# Motherboard.net
KiCad netlist of a schematic drawn in EAGLE
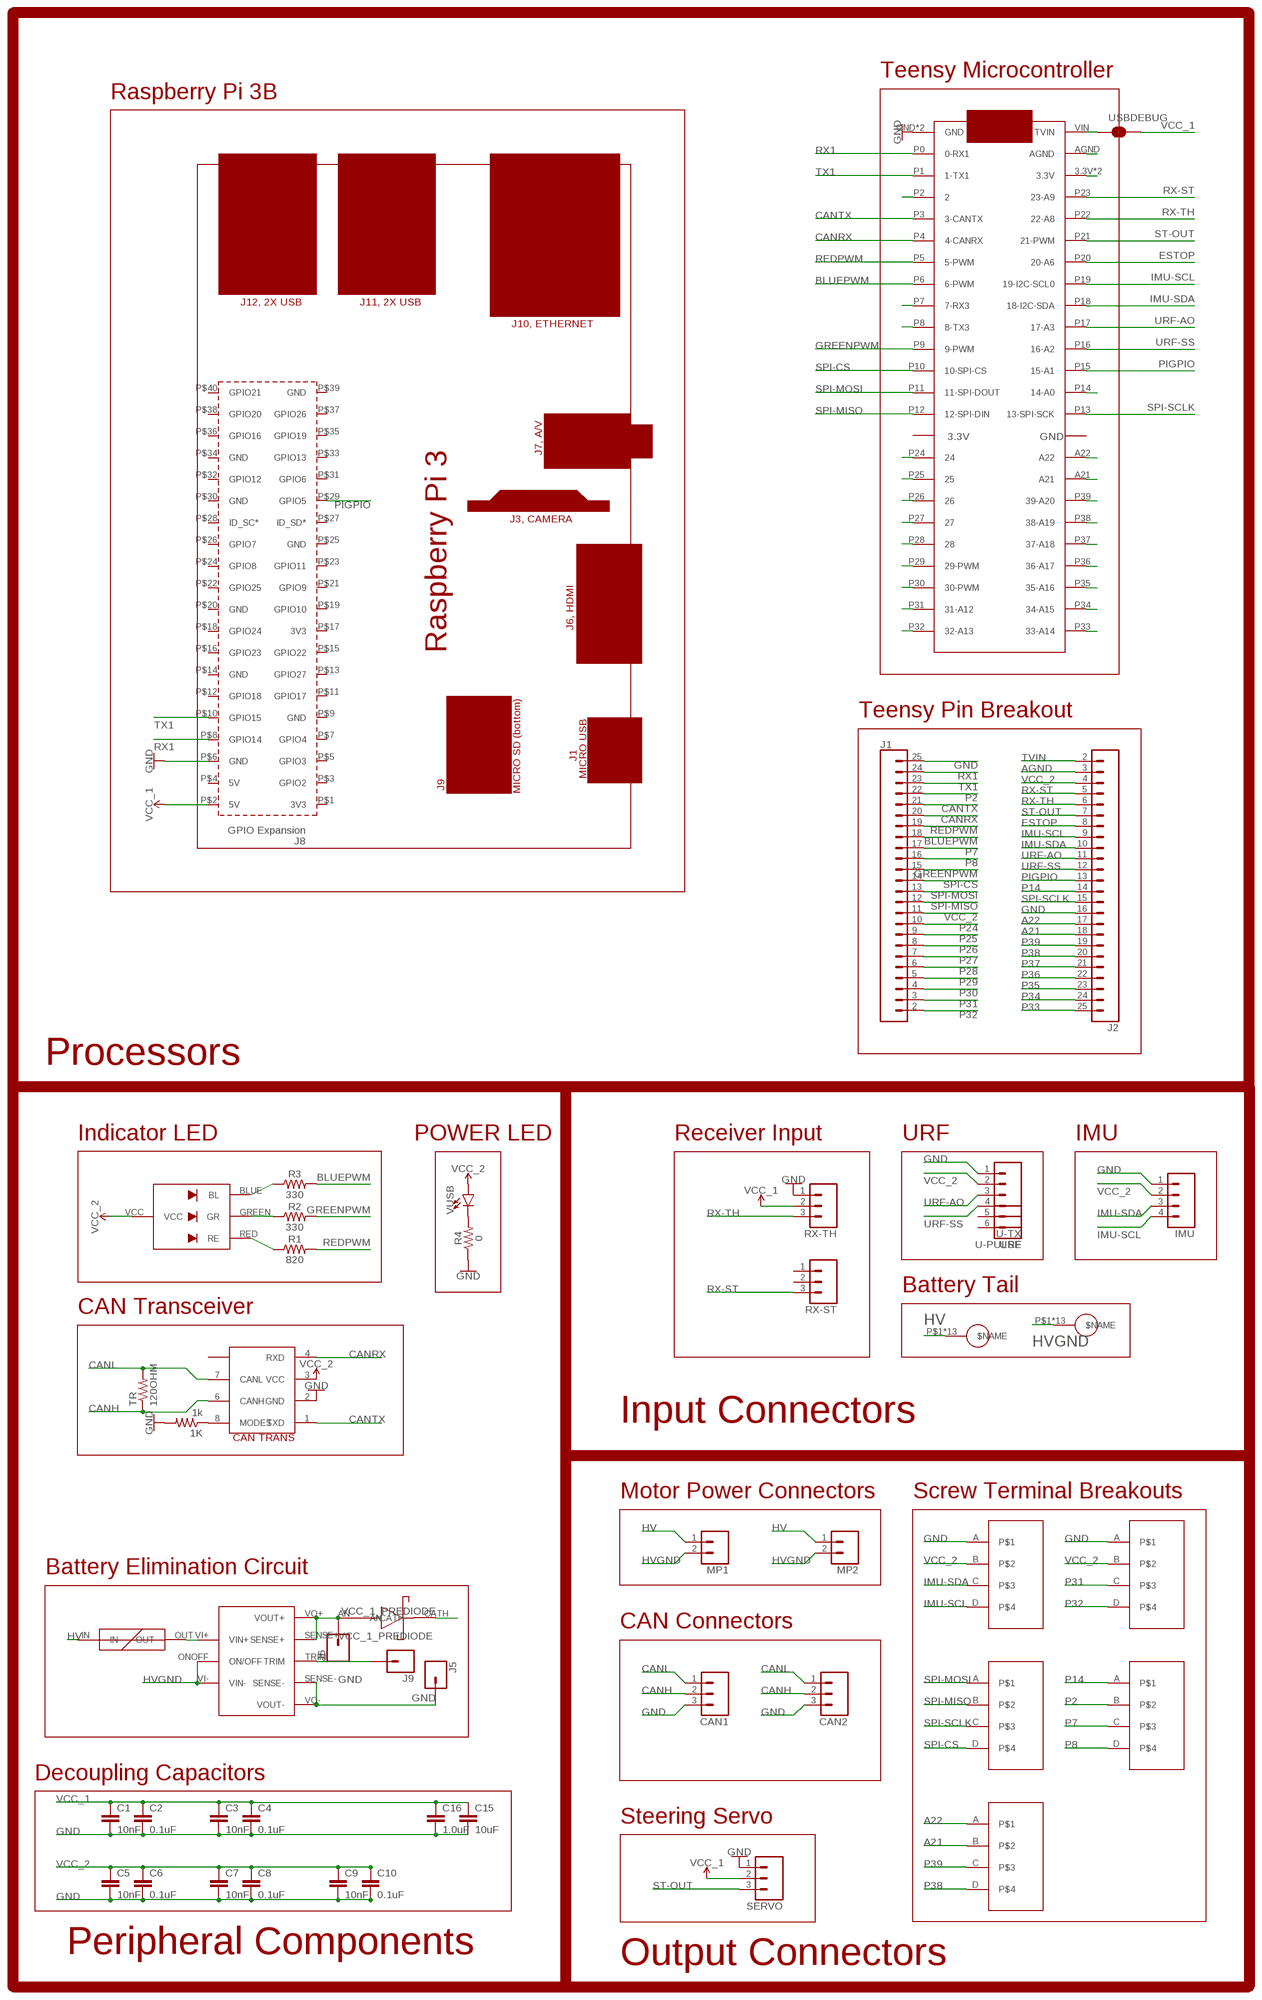
[diagram p0: schematic, sheet 1]

(export (version "E")
  (design (tool "Eeschema 10.0.6"))
  (components
    (comp (ref "1K")
      (value "1k")
      (footprint "eagle-import:R0603")
      (libsource (lib "eagle-import") (part "R-US_R0603"))
    )
    (comp (ref "C1")
      (value "10nF")
      (footprint "eagle-import:0603")
      (libsource (lib "eagle-import") (part "10NF-0603-50V-10%"))
    )
    (comp (ref "C2")
      (value "0.1uF")
      (footprint "eagle-import:0603")
      (libsource (lib "eagle-import") (part "0.1UF-0603-25V-(+80/-20%)"))
    )
    (comp (ref "C3")
      (value "10nF")
      (footprint "eagle-import:0603")
      (libsource (lib "eagle-import") (part "10NF-0603-50V-10%"))
    )
    (comp (ref "C4")
      (value "0.1uF")
      (footprint "eagle-import:0603")
      (libsource (lib "eagle-import") (part "0.1UF-0603-25V-(+80/-20%)"))
    )
    (comp (ref "C5")
      (value "10nF")
      (footprint "eagle-import:0603")
      (libsource (lib "eagle-import") (part "10NF-0603-50V-10%"))
    )
    (comp (ref "C6")
      (value "0.1uF")
      (footprint "eagle-import:0603")
      (libsource (lib "eagle-import") (part "0.1UF-0603-25V-(+80/-20%)"))
    )
    (comp (ref "C7")
      (value "10nF")
      (footprint "eagle-import:0603")
      (libsource (lib "eagle-import") (part "10NF-0603-50V-10%"))
    )
    (comp (ref "C8")
      (value "0.1uF")
      (footprint "eagle-import:0603")
      (libsource (lib "eagle-import") (part "0.1UF-0603-25V-(+80/-20%)"))
    )
    (comp (ref "C9")
      (value "10nF")
      (footprint "eagle-import:0603")
      (libsource (lib "eagle-import") (part "10NF-0603-50V-10%"))
    )
    (comp (ref "C10")
      (value "0.1uF")
      (footprint "eagle-import:0603")
      (libsource (lib "eagle-import") (part "0.1UF-0603-25V-(+80/-20%)"))
    )
    (comp (ref "C15")
      (value "10uF")
      (footprint "eagle-import:1206")
      (libsource (lib "eagle-import") (part "10UF-1206-6.3V-20%"))
    )
    (comp (ref "C16")
      (value "1.0uF")
      (footprint "eagle-import:1206")
      (libsource (lib "eagle-import") (part "1.0UF-1206-50V-10%"))
    )
    (comp (ref "CAN1")
      (value "CONN_03SCREW")
      (footprint "eagle-import:SCREWTERMINAL-3.5MM-3")
      (libsource (lib "eagle-import") (part "CONN_03SCREW"))
    )
    (comp (ref "CAN2")
      (value "CONN_03SCREW")
      (footprint "eagle-import:SCREWTERMINAL-3.5MM-3")
      (libsource (lib "eagle-import") (part "CONN_03SCREW"))
    )
    (comp (ref "DAC/ADC")
      (value "SCREWTERM")
      (footprint "eagle-import:SCREWTERM")
      (libsource (lib "eagle-import") (part "SCREWTERM"))
    )
    (comp (ref "HV+")
      (value "WIREPAD")
      (footprint "eagle-import:WIREPAD")
      (libsource (lib "eagle-import") (part "WIREPAD"))
    )
    (comp (ref "HV-")
      (value "WIREPAD")
      (footprint "eagle-import:WIREPAD")
      (libsource (lib "eagle-import") (part "WIREPAD"))
    )
    (comp (ref "I2C")
      (value "SCREWTERM")
      (footprint "eagle-import:SCREWTERM")
      (libsource (lib "eagle-import") (part "SCREWTERM"))
    )
    (comp (ref "IMU")
      (value "CONN_041X04_NO_SILK")
      (footprint "eagle-import:1X04_NO_SILK")
      (libsource (lib "eagle-import") (part "CONN_041X04_NO_SILK"))
    )
    (comp (ref "J1")
      (value "CONN_24")
      (footprint "eagle-import:1X24")
      (libsource (lib "eagle-import") (part "CONN_24"))
    )
    (comp (ref "J2")
      (value "CONN_24")
      (footprint "eagle-import:1X24")
      (libsource (lib "eagle-import") (part "CONN_24"))
    )
    (comp (ref "J5")
      (value "CONN_01PTH_NO_SILK_YES_STOP")
      (footprint "eagle-import:1X01_NO_SILK")
      (libsource (lib "eagle-import") (part "CONN_01PTH_NO_SILK_YES_STOP"))
    )
    (comp (ref "J6")
      (value "CONN_01PTH_NO_SILK_YES_STOP")
      (footprint "eagle-import:1X01_NO_SILK")
      (libsource (lib "eagle-import") (part "CONN_01PTH_NO_SILK_YES_STOP"))
    )
    (comp (ref "J9")
      (value "CONN_01PTH_NO_SILK_YES_STOP")
      (footprint "eagle-import:1X01_NO_SILK")
      (libsource (lib "eagle-import") (part "CONN_01PTH_NO_SILK_YES_STOP"))
    )
    (comp (ref "MP1")
      (value "CONN_023.5MM")
      (footprint "eagle-import:SCREWTERMINAL-3.5MM-2")
      (libsource (lib "eagle-import") (part "CONN_023.5MM"))
    )
    (comp (ref "MP2")
      (value "CONN_023.5MM")
      (footprint "eagle-import:SCREWTERMINAL-3.5MM-2")
      (libsource (lib "eagle-import") (part "CONN_023.5MM"))
    )
    (comp (ref "PCB1")
      (value "RPI3")
      (footprint "eagle-import:RPI3")
      (libsource (lib "eagle-import") (part "RPI3"))
    )
    (comp (ref "PWM")
      (value "SCREWTERM")
      (footprint "eagle-import:SCREWTERM")
      (libsource (lib "eagle-import") (part "SCREWTERM"))
    )
    (comp (ref "R1")
      (value "820")
      (footprint "eagle-import:0603")
      (libsource (lib "eagle-import") (part "0OHM-0603-1/10W-5%"))
    )
    (comp (ref "R2")
      (value "330")
      (footprint "eagle-import:0603")
      (libsource (lib "eagle-import") (part "0OHM-0603-1/10W-5%"))
    )
    (comp (ref "R3")
      (value "330")
      (footprint "eagle-import:0603")
      (libsource (lib "eagle-import") (part "0OHM-0603-1/10W-5%"))
    )
    (comp (ref "R4")
      (value "0")
      (footprint "eagle-import:0603")
      (libsource (lib "eagle-import") (part "0OHM-0603-1/10W-5%"))
    )
    (comp (ref "RPI-SPI")
      (value "SCREWTERM")
      (footprint "eagle-import:SCREWTERM")
      (libsource (lib "eagle-import") (part "SCREWTERM"))
    )
    (comp (ref "RX-ST")
      (value "CONN_03")
      (footprint "eagle-import:1X03")
      (libsource (lib "eagle-import") (part "CONN_03"))
    )
    (comp (ref "RX-TH")
      (value "CONN_03")
      (footprint "eagle-import:1X03")
      (libsource (lib "eagle-import") (part "CONN_03"))
    )
    (comp (ref "SERVO")
      (value "CONN_03")
      (footprint "eagle-import:1X03")
      (libsource (lib "eagle-import") (part "CONN_03"))
    )
    (comp (ref "TEENS")
      (value "TEENSY3.6")
      (footprint "eagle-import:TEENSY3.6")
      (libsource (lib "eagle-import") (part "TEENSY3.6"))
    )
    (comp (ref "TR")
      (value "120OHM")
      (footprint "eagle-import:R0603")
      (libsource (lib "eagle-import") (part "R-US_R0603"))
    )
    (comp (ref "U$1")
      (value "CREERGB")
      (footprint "eagle-import:CREERGB")
      (libsource (lib "eagle-import") (part "CREERGB"))
    )
    (comp (ref "U$2")
      (value "CAN-TRANS")
      (footprint "eagle-import:SO08")
      (libsource (lib "eagle-import") (part "CAN-TRANS"))
    )
    (comp (ref "U$4")
      (value "BEC")
      (footprint "eagle-import:BEC")
      (libsource (lib "eagle-import") (part "BEC"))
    )
    (comp (ref "U$5")
      (value "LITTLEFUSE")
      (footprint "eagle-import:LITTLEFUSE")
      (libsource (lib "eagle-import") (part "LITTLEFUSE"))
    )
    (comp (ref "U$6")
      (value "SCHOTTKY")
      (footprint "eagle-import:2114")
      (libsource (lib "eagle-import") (part "SCHOTTKY"))
    )
    (comp (ref "U-PULSE")
      (value "CONN_01PTH_NO_SILK_YES_STOP")
      (footprint "eagle-import:1X01_NO_SILK")
      (libsource (lib "eagle-import") (part "CONN_01PTH_NO_SILK_YES_STOP"))
    )
    (comp (ref "U-TX")
      (value "CONN_01PTH_NO_SILK_YES_STOP")
      (footprint "eagle-import:1X01_NO_SILK")
      (libsource (lib "eagle-import") (part "CONN_01PTH_NO_SILK_YES_STOP"))
    )
    (comp (ref "UART")
      (value "SCREWTERM")
      (footprint "eagle-import:SCREWTERM")
      (libsource (lib "eagle-import") (part "SCREWTERM"))
    )
    (comp (ref "URF")
      (value "CONN_06NO_SILK_FEMALE_PTH")
      (footprint "eagle-import:1X06_NO_SILK")
      (libsource (lib "eagle-import") (part "CONN_06NO_SILK_FEMALE_PTH"))
    )
    (comp (ref "USBDEBUG")
      (value "JUMPER-SMT_2_NO_NO-SILK")
      (footprint "eagle-import:SMT-JUMPER_2_NO_NO-SILK")
      (libsource (lib "eagle-import") (part "JUMPER-SMT_2_NO_NO-SILK"))
    )
    (comp (ref "VUSB")
      (value "LED0603")
      (footprint "eagle-import:LED-0603")
      (libsource (lib "eagle-import") (part "LED0603"))
    )
  )
  (nets
    (net (code "1") (name "/A21") (class "Default")
      (node (ref "DAC/ADC") (pin "B") (pinfunction "P$2_B") (pintype "bidirectional"))
      (node (ref "J2") (pin "18") (pinfunction "18_18") (pintype "passive"))
      (node (ref "TEENS") (pin "A21") (pinfunction "A21_A21") (pintype "bidirectional"))
    )
    (net (code "2") (name "/A22") (class "Default")
      (node (ref "DAC/ADC") (pin "A") (pinfunction "P$1_A") (pintype "bidirectional"))
      (node (ref "J2") (pin "17") (pinfunction "17_17") (pintype "passive"))
      (node (ref "TEENS") (pin "A22") (pinfunction "A22_A22") (pintype "bidirectional"))
    )
    (net (code "3") (name "/AGND") (class "Default")
      (node (ref "J2") (pin "3") (pinfunction "3_3") (pintype "passive"))
      (node (ref "TEENS") (pin "AGND") (pinfunction "AGND_AGND") (pintype "bidirectional"))
    )
    (net (code "4") (name "/BLUEPWM") (class "Default")
      (node (ref "J1") (pin "18") (pinfunction "18_18") (pintype "passive"))
      (node (ref "R3") (pin "2") (pinfunction "2_2") (pintype "passive"))
      (node (ref "TEENS") (pin "P6") (pinfunction "6-PWM_P6") (pintype "bidirectional"))
    )
    (net (code "5") (name "/CANH") (class "Default")
      (node (ref "CAN1") (pin "2") (pinfunction "2_2") (pintype "passive"))
      (node (ref "CAN2") (pin "2") (pinfunction "2_2") (pintype "passive"))
      (node (ref "TR") (pin "1") (pinfunction "1_1") (pintype "passive"))
      (node (ref "U$2") (pin "6") (pinfunction "CANH_6") (pintype "bidirectional"))
    )
    (net (code "6") (name "/CANL") (class "Default")
      (node (ref "CAN1") (pin "1") (pinfunction "1_1") (pintype "passive"))
      (node (ref "CAN2") (pin "1") (pinfunction "1_1") (pintype "passive"))
      (node (ref "TR") (pin "2") (pinfunction "2_2") (pintype "passive"))
      (node (ref "U$2") (pin "7") (pinfunction "CANL_7") (pintype "bidirectional"))
    )
    (net (code "7") (name "/CANRX") (class "Default")
      (node (ref "J1") (pin "20") (pinfunction "20_20") (pintype "passive"))
      (node (ref "TEENS") (pin "P4") (pinfunction "4-CANRX_P4") (pintype "bidirectional"))
      (node (ref "U$2") (pin "4") (pinfunction "RXD_4") (pintype "bidirectional"))
    )
    (net (code "8") (name "/CANTX") (class "Default")
      (node (ref "J1") (pin "21") (pinfunction "21_21") (pintype "passive"))
      (node (ref "TEENS") (pin "P3") (pinfunction "3-CANTX_P3") (pintype "bidirectional"))
      (node (ref "U$2") (pin "1") (pinfunction "TXD_1") (pintype "bidirectional"))
    )
    (net (code "9") (name "/ESTOP") (class "Default")
      (node (ref "J2") (pin "8") (pinfunction "8_8") (pintype "passive"))
      (node (ref "TEENS") (pin "P20") (pinfunction "20-A6_P20") (pintype "bidirectional"))
    )
    (net (code "10") (name "/GREENPWM") (class "Default")
      (node (ref "J1") (pin "15") (pinfunction "15_15") (pintype "passive"))
      (node (ref "R2") (pin "2") (pinfunction "2_2") (pintype "passive"))
      (node (ref "TEENS") (pin "P9") (pinfunction "9-PWM_P9") (pintype "bidirectional"))
    )
    (net (code "11") (name "/HV") (class "Default")
      (node (ref "HV+") (pin "P$1") (pinfunction "$NAME_P$1") (pintype "bidirectional"))
      (node (ref "HV+") (pin "P$10") (pinfunction "$NAME_P$10") (pintype "bidirectional"))
      (node (ref "HV+") (pin "P$11") (pinfunction "$NAME_P$11") (pintype "bidirectional"))
      (node (ref "HV+") (pin "P$12") (pinfunction "$NAME_P$12") (pintype "bidirectional"))
      (node (ref "HV+") (pin "P$13") (pinfunction "$NAME_P$13") (pintype "bidirectional"))
      (node (ref "HV+") (pin "P$2") (pinfunction "$NAME_P$2") (pintype "bidirectional"))
      (node (ref "HV+") (pin "P$3") (pinfunction "$NAME_P$3") (pintype "bidirectional"))
      (node (ref "HV+") (pin "P$4") (pinfunction "$NAME_P$4") (pintype "bidirectional"))
      (node (ref "HV+") (pin "P$5") (pinfunction "$NAME_P$5") (pintype "bidirectional"))
      (node (ref "HV+") (pin "P$6") (pinfunction "$NAME_P$6") (pintype "bidirectional"))
      (node (ref "HV+") (pin "P$7") (pinfunction "$NAME_P$7") (pintype "bidirectional"))
      (node (ref "HV+") (pin "P$8") (pinfunction "$NAME_P$8") (pintype "bidirectional"))
      (node (ref "HV+") (pin "P$9") (pinfunction "$NAME_P$9") (pintype "bidirectional"))
      (node (ref "MP1") (pin "1") (pinfunction "1_1") (pintype "passive"))
      (node (ref "MP2") (pin "1") (pinfunction "1_1") (pintype "passive"))
      (node (ref "U$5") (pin "IN") (pinfunction "IN_IN") (pintype "bidirectional"))
    )
    (net (code "12") (name "/HVGND") (class "Default")
      (node (ref "HV-") (pin "P$1") (pinfunction "$NAME_P$1") (pintype "bidirectional"))
      (node (ref "HV-") (pin "P$10") (pinfunction "$NAME_P$10") (pintype "bidirectional"))
      (node (ref "HV-") (pin "P$11") (pinfunction "$NAME_P$11") (pintype "bidirectional"))
      (node (ref "HV-") (pin "P$12") (pinfunction "$NAME_P$12") (pintype "bidirectional"))
      (node (ref "HV-") (pin "P$13") (pinfunction "$NAME_P$13") (pintype "bidirectional"))
      (node (ref "HV-") (pin "P$2") (pinfunction "$NAME_P$2") (pintype "bidirectional"))
      (node (ref "HV-") (pin "P$3") (pinfunction "$NAME_P$3") (pintype "bidirectional"))
      (node (ref "HV-") (pin "P$4") (pinfunction "$NAME_P$4") (pintype "bidirectional"))
      (node (ref "HV-") (pin "P$5") (pinfunction "$NAME_P$5") (pintype "bidirectional"))
      (node (ref "HV-") (pin "P$6") (pinfunction "$NAME_P$6") (pintype "bidirectional"))
      (node (ref "HV-") (pin "P$7") (pinfunction "$NAME_P$7") (pintype "bidirectional"))
      (node (ref "HV-") (pin "P$8") (pinfunction "$NAME_P$8") (pintype "bidirectional"))
      (node (ref "HV-") (pin "P$9") (pinfunction "$NAME_P$9") (pintype "bidirectional"))
      (node (ref "MP1") (pin "2") (pinfunction "2_2") (pintype "passive"))
      (node (ref "MP2") (pin "2") (pinfunction "2_2") (pintype "passive"))
      (node (ref "U$4") (pin "ONOFF") (pinfunction "ON/OFF_ONOFF") (pintype "bidirectional"))
      (node (ref "U$4") (pin "VI-") (pinfunction "VIN-_VI-") (pintype "bidirectional"))
    )
    (net (code "13") (name "/IMU-SCL") (class "Default")
      (node (ref "I2C") (pin "D") (pinfunction "P$4_D") (pintype "bidirectional"))
      (node (ref "IMU") (pin "4") (pinfunction "4_4") (pintype "passive"))
      (node (ref "J2") (pin "9") (pinfunction "9_9") (pintype "passive"))
      (node (ref "TEENS") (pin "P19") (pinfunction "19-I2C-SCL0_P19") (pintype "bidirectional"))
    )
    (net (code "14") (name "/IMU-SDA") (class "Default")
      (node (ref "I2C") (pin "C") (pinfunction "P$3_C") (pintype "bidirectional"))
      (node (ref "IMU") (pin "3") (pinfunction "3_3") (pintype "passive"))
      (node (ref "J2") (pin "10") (pinfunction "10_10") (pintype "passive"))
      (node (ref "TEENS") (pin "P18") (pinfunction "18-I2C-SDA_P18") (pintype "bidirectional"))
    )
    (net (code "15") (name "/P2") (class "Default")
      (node (ref "J1") (pin "22") (pinfunction "22_22") (pintype "passive"))
      (node (ref "PWM") (pin "B") (pinfunction "P$2_B") (pintype "bidirectional"))
      (node (ref "TEENS") (pin "P2") (pinfunction "2_P2") (pintype "bidirectional"))
    )
    (net (code "16") (name "/P7") (class "Default")
      (node (ref "J1") (pin "17") (pinfunction "17_17") (pintype "passive"))
      (node (ref "PWM") (pin "C") (pinfunction "P$3_C") (pintype "bidirectional"))
      (node (ref "TEENS") (pin "P7") (pinfunction "7-RX3_P7") (pintype "bidirectional"))
    )
    (net (code "17") (name "/P8") (class "Default")
      (node (ref "J1") (pin "16") (pinfunction "16_16") (pintype "passive"))
      (node (ref "PWM") (pin "D") (pinfunction "P$4_D") (pintype "bidirectional"))
      (node (ref "TEENS") (pin "P8") (pinfunction "8-TX3_P8") (pintype "bidirectional"))
    )
    (net (code "18") (name "/P14") (class "Default")
      (node (ref "J2") (pin "14") (pinfunction "14_14") (pintype "passive"))
      (node (ref "PWM") (pin "A") (pinfunction "P$1_A") (pintype "bidirectional"))
      (node (ref "TEENS") (pin "P14") (pinfunction "14-A0_P14") (pintype "bidirectional"))
    )
    (net (code "19") (name "/P24") (class "Default")
      (node (ref "J1") (pin "10") (pinfunction "10_10") (pintype "passive"))
      (node (ref "TEENS") (pin "P24") (pinfunction "24_P24") (pintype "bidirectional"))
    )
    (net (code "20") (name "/P25") (class "Default")
      (node (ref "J1") (pin "9") (pinfunction "9_9") (pintype "passive"))
      (node (ref "TEENS") (pin "P25") (pinfunction "25_P25") (pintype "bidirectional"))
    )
    (net (code "21") (name "/P26") (class "Default")
      (node (ref "J1") (pin "8") (pinfunction "8_8") (pintype "passive"))
      (node (ref "TEENS") (pin "P26") (pinfunction "26_P26") (pintype "bidirectional"))
    )
    (net (code "22") (name "/P27") (class "Default")
      (node (ref "J1") (pin "7") (pinfunction "7_7") (pintype "passive"))
      (node (ref "TEENS") (pin "P27") (pinfunction "27_P27") (pintype "bidirectional"))
    )
    (net (code "23") (name "/P28") (class "Default")
      (node (ref "J1") (pin "6") (pinfunction "6_6") (pintype "passive"))
      (node (ref "TEENS") (pin "P28") (pinfunction "28_P28") (pintype "bidirectional"))
    )
    (net (code "24") (name "/P29") (class "Default")
      (node (ref "J1") (pin "5") (pinfunction "5_5") (pintype "passive"))
      (node (ref "TEENS") (pin "P29") (pinfunction "29-PWM_P29") (pintype "bidirectional"))
    )
    (net (code "25") (name "/P30") (class "Default")
      (node (ref "J1") (pin "4") (pinfunction "4_4") (pintype "passive"))
      (node (ref "TEENS") (pin "P30") (pinfunction "30-PWM_P30") (pintype "bidirectional"))
    )
    (net (code "26") (name "/P31") (class "Default")
      (node (ref "J1") (pin "3") (pinfunction "3_3") (pintype "passive"))
      (node (ref "TEENS") (pin "P31") (pinfunction "31-A12_P31") (pintype "bidirectional"))
      (node (ref "UART") (pin "C") (pinfunction "P$3_C") (pintype "bidirectional"))
    )
    (net (code "27") (name "/P32") (class "Default")
      (node (ref "J1") (pin "2") (pinfunction "2_2") (pintype "passive"))
      (node (ref "TEENS") (pin "P32") (pinfunction "32-A13_P32") (pintype "bidirectional"))
      (node (ref "UART") (pin "D") (pinfunction "P$4_D") (pintype "bidirectional"))
    )
    (net (code "28") (name "/P33") (class "Default")
      (node (ref "J2") (pin "25") (pinfunction "25_25") (pintype "passive"))
      (node (ref "TEENS") (pin "P33") (pinfunction "33-A14_P33") (pintype "bidirectional"))
    )
    (net (code "29") (name "/P34") (class "Default")
      (node (ref "J2") (pin "24") (pinfunction "24_24") (pintype "passive"))
      (node (ref "TEENS") (pin "P34") (pinfunction "34-A15_P34") (pintype "bidirectional"))
    )
    (net (code "30") (name "/P35") (class "Default")
      (node (ref "J2") (pin "23") (pinfunction "23_23") (pintype "passive"))
      (node (ref "TEENS") (pin "P35") (pinfunction "35-A16_P35") (pintype "bidirectional"))
    )
    (net (code "31") (name "/P36") (class "Default")
      (node (ref "J2") (pin "22") (pinfunction "22_22") (pintype "passive"))
      (node (ref "TEENS") (pin "P36") (pinfunction "36-A17_P36") (pintype "bidirectional"))
    )
    (net (code "32") (name "/P37") (class "Default")
      (node (ref "J2") (pin "21") (pinfunction "21_21") (pintype "passive"))
      (node (ref "TEENS") (pin "P37") (pinfunction "37-A18_P37") (pintype "bidirectional"))
    )
    (net (code "33") (name "/P38") (class "Default")
      (node (ref "DAC/ADC") (pin "D") (pinfunction "P$4_D") (pintype "bidirectional"))
      (node (ref "J2") (pin "20") (pinfunction "20_20") (pintype "passive"))
      (node (ref "TEENS") (pin "P38") (pinfunction "38-A19_P38") (pintype "bidirectional"))
    )
    (net (code "34") (name "/P39") (class "Default")
      (node (ref "DAC/ADC") (pin "C") (pinfunction "P$3_C") (pintype "bidirectional"))
      (node (ref "J2") (pin "19") (pinfunction "19_19") (pintype "passive"))
      (node (ref "TEENS") (pin "P39") (pinfunction "39-A20_P39") (pintype "bidirectional"))
    )
    (net (code "35") (name "/PIGPIO") (class "Default")
      (node (ref "J2") (pin "13") (pinfunction "13_13") (pintype "passive"))
      (node (ref "PCB1") (pin "P$29") (pinfunction "GPIO5_P$29") (pintype "bidirectional"))
      (node (ref "TEENS") (pin "P15") (pinfunction "15-A1_P15") (pintype "bidirectional"))
    )
    (net (code "36") (name "/REDPWM") (class "Default")
      (node (ref "J1") (pin "19") (pinfunction "19_19") (pintype "passive"))
      (node (ref "R1") (pin "2") (pinfunction "2_2") (pintype "passive"))
      (node (ref "TEENS") (pin "P5") (pinfunction "5-PWM_P5") (pintype "bidirectional"))
    )
    (net (code "37") (name "/RX-ST") (class "Default")
      (node (ref "J2") (pin "5") (pinfunction "5_5") (pintype "passive"))
      (node (ref "RX-ST") (pin "3") (pinfunction "3_3") (pintype "passive"))
      (node (ref "TEENS") (pin "P23") (pinfunction "23-A9_P23") (pintype "bidirectional"))
    )
    (net (code "38") (name "/RX-TH") (class "Default")
      (node (ref "J2") (pin "6") (pinfunction "6_6") (pintype "passive"))
      (node (ref "RX-TH") (pin "3") (pinfunction "3_3") (pintype "passive"))
      (node (ref "TEENS") (pin "P22") (pinfunction "22-A8_P22") (pintype "bidirectional"))
    )
    (net (code "39") (name "/RX1") (class "Default")
      (node (ref "J1") (pin "24") (pinfunction "24_24") (pintype "passive"))
      (node (ref "PCB1") (pin "P$8") (pinfunction "GPIO14_P$8") (pintype "bidirectional"))
      (node (ref "TEENS") (pin "P0") (pinfunction "0-RX1_P0") (pintype "bidirectional"))
    )
    (net (code "40") (name "/SPI-CS") (class "Default")
      (node (ref "J1") (pin "14") (pinfunction "14_14") (pintype "passive"))
      (node (ref "RPI-SPI") (pin "D") (pinfunction "P$4_D") (pintype "bidirectional"))
      (node (ref "TEENS") (pin "P10") (pinfunction "10-SPI-CS_P10") (pintype "bidirectional"))
    )
    (net (code "41") (name "/SPI-MISO") (class "Default")
      (node (ref "J1") (pin "12") (pinfunction "12_12") (pintype "passive"))
      (node (ref "RPI-SPI") (pin "B") (pinfunction "P$2_B") (pintype "bidirectional"))
      (node (ref "TEENS") (pin "P12") (pinfunction "12-SPI-DIN_P12") (pintype "bidirectional"))
    )
    (net (code "42") (name "/SPI-MOSI") (class "Default")
      (node (ref "J1") (pin "13") (pinfunction "13_13") (pintype "passive"))
      (node (ref "RPI-SPI") (pin "A") (pinfunction "P$1_A") (pintype "bidirectional"))
      (node (ref "TEENS") (pin "P11") (pinfunction "11-SPI-DOUT_P11") (pintype "bidirectional"))
    )
    (net (code "43") (name "/SPI-SCLK") (class "Default")
      (node (ref "J2") (pin "15") (pinfunction "15_15") (pintype "passive"))
      (node (ref "RPI-SPI") (pin "C") (pinfunction "P$3_C") (pintype "bidirectional"))
      (node (ref "TEENS") (pin "P13") (pinfunction "13-SPI-SCK_P13") (pintype "bidirectional"))
    )
    (net (code "44") (name "/ST-OUT") (class "Default")
      (node (ref "J2") (pin "7") (pinfunction "7_7") (pintype "passive"))
      (node (ref "SERVO") (pin "3") (pinfunction "3_3") (pintype "passive"))
      (node (ref "TEENS") (pin "P21") (pinfunction "21-PWM_P21") (pintype "bidirectional"))
    )
    (net (code "45") (name "/TVIN") (class "Default")
      (node (ref "J2") (pin "2") (pinfunction "2_2") (pintype "passive"))
      (node (ref "TEENS") (pin "VIN") (pinfunction "TVIN_VIN") (pintype "bidirectional"))
      (node (ref "USBDEBUG") (pin "1") (pinfunction "1_1") (pintype "passive"))
    )
    (net (code "46") (name "/TX1") (class "Default")
      (node (ref "J1") (pin "23") (pinfunction "23_23") (pintype "passive"))
      (node (ref "PCB1") (pin "P$10") (pinfunction "GPIO15_P$10") (pintype "bidirectional"))
      (node (ref "TEENS") (pin "P1") (pinfunction "1-TX1_P1") (pintype "bidirectional"))
    )
    (net (code "47") (name "/URF-AO") (class "Default")
      (node (ref "J2") (pin "11") (pinfunction "11_11") (pintype "passive"))
      (node (ref "TEENS") (pin "P17") (pinfunction "17-A3_P17") (pintype "bidirectional"))
      (node (ref "URF") (pin "3") (pinfunction "3_3") (pintype "passive"))
    )
    (net (code "48") (name "/URF-SS") (class "Default")
      (node (ref "J2") (pin "12") (pinfunction "12_12") (pintype "passive"))
      (node (ref "TEENS") (pin "P16") (pinfunction "16-A2_P16") (pintype "bidirectional"))
      (node (ref "URF") (pin "4") (pinfunction "4_4") (pintype "passive"))
    )
    (net (code "49") (name "/VCC_1_PREDIODE") (class "Default")
      (node (ref "J6") (pin "1") (pinfunction "1_1") (pintype "passive"))
      (node (ref "U$4") (pin "SENSE+") (pinfunction "SENSE+_SENSE+") (pintype "bidirectional"))
      (node (ref "U$4") (pin "VO+") (pinfunction "VOUT+_VO+") (pintype "bidirectional"))
      (node (ref "U$6") (pin "AN") (pinfunction "AN_AN") (pintype "bidirectional"))
    )
    (net (code "50") (name "GND") (class "Default")
      (node (ref "1K") (pin "2") (pinfunction "2_2") (pintype "passive"))
      (node (ref "C1") (pin "2") (pinfunction "2_2") (pintype "passive"))
      (node (ref "C10") (pin "2") (pinfunction "2_2") (pintype "passive"))
      (node (ref "C15") (pin "2") (pinfunction "2_2") (pintype "passive"))
      (node (ref "C16") (pin "2") (pinfunction "2_2") (pintype "passive"))
      (node (ref "C2") (pin "2") (pinfunction "2_2") (pintype "passive"))
      (node (ref "C3") (pin "2") (pinfunction "2_2") (pintype "passive"))
      (node (ref "C4") (pin "2") (pinfunction "2_2") (pintype "passive"))
      (node (ref "C5") (pin "2") (pinfunction "2_2") (pintype "passive"))
      (node (ref "C6") (pin "2") (pinfunction "2_2") (pintype "passive"))
      (node (ref "C7") (pin "2") (pinfunction "2_2") (pintype "passive"))
      (node (ref "C8") (pin "2") (pinfunction "2_2") (pintype "passive"))
      (node (ref "C9") (pin "2") (pinfunction "2_2") (pintype "passive"))
      (node (ref "CAN1") (pin "3") (pinfunction "3_3") (pintype "passive"))
      (node (ref "CAN2") (pin "3") (pinfunction "3_3") (pintype "passive"))
      (node (ref "I2C") (pin "A") (pinfunction "P$1_A") (pintype "bidirectional"))
      (node (ref "IMU") (pin "1") (pinfunction "1_1") (pintype "passive"))
      (node (ref "J1") (pin "25") (pinfunction "25_25") (pintype "passive"))
      (node (ref "J2") (pin "16") (pinfunction "16_16") (pintype "passive"))
      (node (ref "J5") (pin "1") (pinfunction "1_1") (pintype "passive"))
      (node (ref "PCB1") (pin "P$6") (pinfunction "GND_P$6") (pintype "bidirectional"))
      (node (ref "R4") (pin "1") (pinfunction "1_1") (pintype "passive"))
      (node (ref "RX-TH") (pin "1") (pinfunction "1_1") (pintype "passive"))
      (node (ref "SERVO") (pin "1") (pinfunction "1_1") (pintype "passive"))
      (node (ref "TEENS") (pin "GND") (pinfunction "GND_GND") (pintype "bidirectional"))
      (node (ref "TEENS") (pin "GND2") (pinfunction "GND_GND2") (pintype "bidirectional"))
      (node (ref "U$2") (pin "2") (pinfunction "GND_2") (pintype "bidirectional"))
      (node (ref "U$4") (pin "SENSE-") (pinfunction "SENSE-_SENSE-") (pintype "bidirectional"))
      (node (ref "U$4") (pin "VO-") (pinfunction "VOUT-_VO-") (pintype "bidirectional"))
      (node (ref "UART") (pin "A") (pinfunction "P$1_A") (pintype "bidirectional"))
      (node (ref "URF") (pin "1") (pinfunction "1_1") (pintype "passive"))
    )
    (net (code "51") (name "Net-(J9-Pad1)") (class "Default")
      (node (ref "J9") (pin "1") (pinfunction "1_1") (pintype "passive"))
      (node (ref "U$4") (pin "TRIM") (pinfunction "TRIM_TRIM") (pintype "bidirectional"))
    )
    (net (code "52") (name "Net-(R4-Pad2)") (class "Default")
      (node (ref "R4") (pin "2") (pinfunction "2_2") (pintype "passive"))
      (node (ref "VUSB") (pin "C") (pinfunction "C_C") (pintype "passive"))
    )
    (net (code "53") (name "Net-(U$1-BL)") (class "Default")
      (node (ref "R3") (pin "1") (pinfunction "1_1") (pintype "passive"))
      (node (ref "U$1") (pin "BLUE") (pinfunction "BL_BLUE") (pintype "bidirectional"))
    )
    (net (code "54") (name "Net-(U$1-GR)") (class "Default")
      (node (ref "R2") (pin "1") (pinfunction "1_1") (pintype "passive"))
      (node (ref "U$1") (pin "GREEN") (pinfunction "GR_GREEN") (pintype "bidirectional"))
    )
    (net (code "55") (name "Net-(U$1-RE)") (class "Default")
      (node (ref "R1") (pin "1") (pinfunction "1_1") (pintype "passive"))
      (node (ref "U$1") (pin "RED") (pinfunction "RE_RED") (pintype "bidirectional"))
    )
    (net (code "56") (name "Net-(U$2-MODES)") (class "Default")
      (node (ref "1K") (pin "1") (pinfunction "1_1") (pintype "passive"))
      (node (ref "U$2") (pin "8") (pinfunction "MODES_8") (pintype "bidirectional"))
    )
    (net (code "57") (name "Net-(U$4-VIN+)") (class "Default")
      (node (ref "U$4") (pin "VI+") (pinfunction "VIN+_VI+") (pintype "bidirectional"))
      (node (ref "U$5") (pin "OUT") (pinfunction "OUT_OUT") (pintype "bidirectional"))
    )
    (net (code "58") (name "Net-(U-PULSE-Pad1)") (class "Default")
      (node (ref "U-PULSE") (pin "1") (pinfunction "1_1") (pintype "passive"))
      (node (ref "URF") (pin "6") (pinfunction "6_6") (pintype "passive"))
    )
    (net (code "59") (name "Net-(U-TX-Pad1)") (class "Default")
      (node (ref "U-TX") (pin "1") (pinfunction "1_1") (pintype "passive"))
      (node (ref "URF") (pin "5") (pinfunction "5_5") (pintype "passive"))
    )
    (net (code "60") (name "VCC_1") (class "Default")
      (node (ref "C1") (pin "1") (pinfunction "1_1") (pintype "passive"))
      (node (ref "C15") (pin "1") (pinfunction "1_1") (pintype "passive"))
      (node (ref "C16") (pin "1") (pinfunction "1_1") (pintype "passive"))
      (node (ref "C2") (pin "1") (pinfunction "1_1") (pintype "passive"))
      (node (ref "C3") (pin "1") (pinfunction "1_1") (pintype "passive"))
      (node (ref "C4") (pin "1") (pinfunction "1_1") (pintype "passive"))
      (node (ref "PCB1") (pin "P$2") (pinfunction "5V_P$2") (pintype "bidirectional"))
      (node (ref "RX-TH") (pin "2") (pinfunction "2_2") (pintype "passive"))
      (node (ref "SERVO") (pin "2") (pinfunction "2_2") (pintype "passive"))
      (node (ref "U$6") (pin "CATH") (pinfunction "CATH_CATH") (pintype "bidirectional"))
      (node (ref "USBDEBUG") (pin "2") (pinfunction "2_2") (pintype "passive"))
    )
    (net (code "61") (name "VCC_2") (class "Default")
      (node (ref "C10") (pin "1") (pinfunction "1_1") (pintype "passive"))
      (node (ref "C5") (pin "1") (pinfunction "1_1") (pintype "passive"))
      (node (ref "C6") (pin "1") (pinfunction "1_1") (pintype "passive"))
      (node (ref "C7") (pin "1") (pinfunction "1_1") (pintype "passive"))
      (node (ref "C8") (pin "1") (pinfunction "1_1") (pintype "passive"))
      (node (ref "C9") (pin "1") (pinfunction "1_1") (pintype "passive"))
      (node (ref "I2C") (pin "B") (pinfunction "P$2_B") (pintype "bidirectional"))
      (node (ref "IMU") (pin "2") (pinfunction "2_2") (pintype "passive"))
      (node (ref "J1") (pin "11") (pinfunction "11_11") (pintype "passive"))
      (node (ref "J2") (pin "4") (pinfunction "4_4") (pintype "passive"))
      (node (ref "TEENS") (pin "3.3V") (pinfunction "3.3V_3.3V") (pintype "bidirectional"))
      (node (ref "TEENS") (pin "3.3V2") (pinfunction "3.3V_3.3V2") (pintype "bidirectional"))
      (node (ref "U$1") (pin "VCC") (pinfunction "VCC_VCC") (pintype "bidirectional"))
      (node (ref "U$2") (pin "3") (pinfunction "VCC_3") (pintype "bidirectional"))
      (node (ref "UART") (pin "B") (pinfunction "P$2_B") (pintype "bidirectional"))
      (node (ref "URF") (pin "2") (pinfunction "2_2") (pintype "passive"))
      (node (ref "VUSB") (pin "A") (pinfunction "A_A") (pintype "passive"))
    )
    (net (code "62") (name "unconnected-(PCB1-3V3-PadP$1)") (class "Default")
      (node (ref "PCB1") (pin "P$1") (pinfunction "3V3_P$1") (pintype "bidirectional"))
    )
    (net (code "63") (name "unconnected-(PCB1-3V3-PadP$17)") (class "Default")
      (node (ref "PCB1") (pin "P$17") (pinfunction "3V3_P$17") (pintype "bidirectional"))
    )
    (net (code "64") (name "unconnected-(PCB1-5V-PadP$4)") (class "Default")
      (node (ref "PCB1") (pin "P$4") (pinfunction "5V_P$4") (pintype "bidirectional"))
    )
    (net (code "65") (name "unconnected-(PCB1-GND-PadP$9)") (class "Default")
      (node (ref "PCB1") (pin "P$9") (pinfunction "GND_P$9") (pintype "bidirectional"))
    )
    (net (code "66") (name "unconnected-(PCB1-GND-PadP$14)") (class "Default")
      (node (ref "PCB1") (pin "P$14") (pinfunction "GND_P$14") (pintype "bidirectional"))
    )
    (net (code "67") (name "unconnected-(PCB1-GND-PadP$20)") (class "Default")
      (node (ref "PCB1") (pin "P$20") (pinfunction "GND_P$20") (pintype "bidirectional"))
    )
    (net (code "68") (name "unconnected-(PCB1-GND-PadP$25)") (class "Default")
      (node (ref "PCB1") (pin "P$25") (pinfunction "GND_P$25") (pintype "bidirectional"))
    )
    (net (code "69") (name "unconnected-(PCB1-GND-PadP$30)") (class "Default")
      (node (ref "PCB1") (pin "P$30") (pinfunction "GND_P$30") (pintype "bidirectional"))
    )
    (net (code "70") (name "unconnected-(PCB1-GND-PadP$34)") (class "Default")
      (node (ref "PCB1") (pin "P$34") (pinfunction "GND_P$34") (pintype "bidirectional"))
    )
    (net (code "71") (name "unconnected-(PCB1-GND-PadP$39)") (class "Default")
      (node (ref "PCB1") (pin "P$39") (pinfunction "GND_P$39") (pintype "bidirectional"))
    )
    (net (code "72") (name "unconnected-(PCB1-GPIO2-PadP$3)") (class "Default")
      (node (ref "PCB1") (pin "P$3") (pinfunction "GPIO2_P$3") (pintype "bidirectional"))
    )
    (net (code "73") (name "unconnected-(PCB1-GPIO3-PadP$5)") (class "Default")
      (node (ref "PCB1") (pin "P$5") (pinfunction "GPIO3_P$5") (pintype "bidirectional"))
    )
    (net (code "74") (name "unconnected-(PCB1-GPIO4-PadP$7)") (class "Default")
      (node (ref "PCB1") (pin "P$7") (pinfunction "GPIO4_P$7") (pintype "bidirectional"))
    )
    (net (code "75") (name "unconnected-(PCB1-GPIO6-PadP$31)") (class "Default")
      (node (ref "PCB1") (pin "P$31") (pinfunction "GPIO6_P$31") (pintype "bidirectional"))
    )
    (net (code "76") (name "unconnected-(PCB1-GPIO7-PadP$26)") (class "Default")
      (node (ref "PCB1") (pin "P$26") (pinfunction "GPIO7_P$26") (pintype "bidirectional"))
    )
    (net (code "77") (name "unconnected-(PCB1-GPIO8-PadP$24)") (class "Default")
      (node (ref "PCB1") (pin "P$24") (pinfunction "GPIO8_P$24") (pintype "bidirectional"))
    )
    (net (code "78") (name "unconnected-(PCB1-GPIO9-PadP$21)") (class "Default")
      (node (ref "PCB1") (pin "P$21") (pinfunction "GPIO9_P$21") (pintype "bidirectional"))
    )
    (net (code "79") (name "unconnected-(PCB1-GPIO10-PadP$19)") (class "Default")
      (node (ref "PCB1") (pin "P$19") (pinfunction "GPIO10_P$19") (pintype "bidirectional"))
    )
    (net (code "80") (name "unconnected-(PCB1-GPIO11-PadP$23)") (class "Default")
      (node (ref "PCB1") (pin "P$23") (pinfunction "GPIO11_P$23") (pintype "bidirectional"))
    )
    (net (code "81") (name "unconnected-(PCB1-GPIO12-PadP$32)") (class "Default")
      (node (ref "PCB1") (pin "P$32") (pinfunction "GPIO12_P$32") (pintype "bidirectional"))
    )
    (net (code "82") (name "unconnected-(PCB1-GPIO13-PadP$33)") (class "Default")
      (node (ref "PCB1") (pin "P$33") (pinfunction "GPIO13_P$33") (pintype "bidirectional"))
    )
    (net (code "83") (name "unconnected-(PCB1-GPIO16-PadP$36)") (class "Default")
      (node (ref "PCB1") (pin "P$36") (pinfunction "GPIO16_P$36") (pintype "bidirectional"))
    )
    (net (code "84") (name "unconnected-(PCB1-GPIO17-PadP$11)") (class "Default")
      (node (ref "PCB1") (pin "P$11") (pinfunction "GPIO17_P$11") (pintype "bidirectional"))
    )
    (net (code "85") (name "unconnected-(PCB1-GPIO18-PadP$12)") (class "Default")
      (node (ref "PCB1") (pin "P$12") (pinfunction "GPIO18_P$12") (pintype "bidirectional"))
    )
    (net (code "86") (name "unconnected-(PCB1-GPIO19-PadP$35)") (class "Default")
      (node (ref "PCB1") (pin "P$35") (pinfunction "GPIO19_P$35") (pintype "bidirectional"))
    )
    (net (code "87") (name "unconnected-(PCB1-GPIO20-PadP$38)") (class "Default")
      (node (ref "PCB1") (pin "P$38") (pinfunction "GPIO20_P$38") (pintype "bidirectional"))
    )
    (net (code "88") (name "unconnected-(PCB1-GPIO21-PadP$40)") (class "Default")
      (node (ref "PCB1") (pin "P$40") (pinfunction "GPIO21_P$40") (pintype "bidirectional"))
    )
    (net (code "89") (name "unconnected-(PCB1-GPIO22-PadP$15)") (class "Default")
      (node (ref "PCB1") (pin "P$15") (pinfunction "GPIO22_P$15") (pintype "bidirectional"))
    )
    (net (code "90") (name "unconnected-(PCB1-GPIO23-PadP$16)") (class "Default")
      (node (ref "PCB1") (pin "P$16") (pinfunction "GPIO23_P$16") (pintype "bidirectional"))
    )
    (net (code "91") (name "unconnected-(PCB1-GPIO24-PadP$18)") (class "Default")
      (node (ref "PCB1") (pin "P$18") (pinfunction "GPIO24_P$18") (pintype "bidirectional"))
    )
    (net (code "92") (name "unconnected-(PCB1-GPIO25-PadP$22)") (class "Default")
      (node (ref "PCB1") (pin "P$22") (pinfunction "GPIO25_P$22") (pintype "bidirectional"))
    )
    (net (code "93") (name "unconnected-(PCB1-GPIO26-PadP$37)") (class "Default")
      (node (ref "PCB1") (pin "P$37") (pinfunction "GPIO26_P$37") (pintype "bidirectional"))
    )
    (net (code "94") (name "unconnected-(PCB1-GPIO27-PadP$13)") (class "Default")
      (node (ref "PCB1") (pin "P$13") (pinfunction "GPIO27_P$13") (pintype "bidirectional"))
    )
    (net (code "95") (name "unconnected-(PCB1-ID_SC*-PadP$28)") (class "Default")
      (node (ref "PCB1") (pin "P$28") (pinfunction "ID_SC*_P$28") (pintype "bidirectional"))
    )
    (net (code "96") (name "unconnected-(PCB1-ID_SD*-PadP$27)") (class "Default")
      (node (ref "PCB1") (pin "P$27") (pinfunction "ID_SD*_P$27") (pintype "bidirectional"))
    )
    (net (code "97") (name "unconnected-(RX-ST-Pad1)") (class "Default")
      (node (ref "RX-ST") (pin "1") (pinfunction "1_1") (pintype "passive"))
    )
    (net (code "98") (name "unconnected-(RX-ST-Pad2)") (class "Default")
      (node (ref "RX-ST") (pin "2") (pinfunction "2_2") (pintype "passive"))
    )
  )
)
